# basic_attiny85.net
KiCad netlist of a schematic drawn in EAGLE
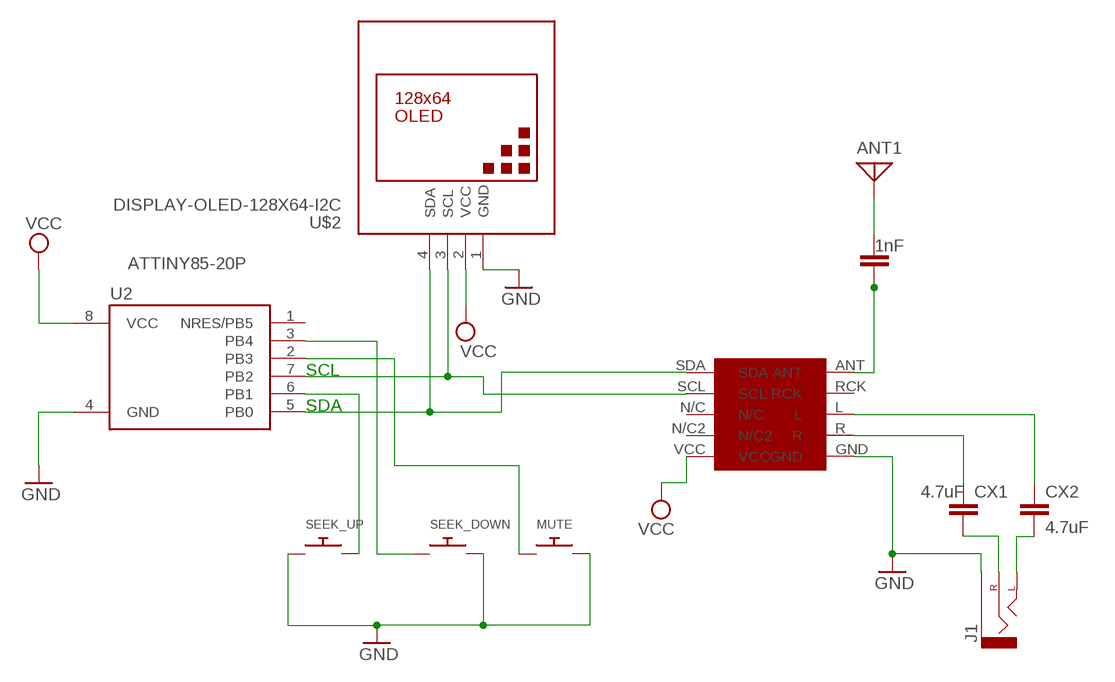
[diagram p0: schematic, sheet 1]

(export (version "E")
  (design (tool "Eeschema 10.0.6"))
  (components
    (comp (ref "ANT1")
      (value "ANTENNA")
      (footprint "eagle-import:PAD-01")
      (libsource (lib "eagle-import") (part "ANTENNA"))
    )
    (comp (ref "CX1")
      (value "4.7uF")
      (footprint "eagle-import:XC10B6")
      (libsource (lib "eagle-import") (part "CXXC10B6"))
    )
    (comp (ref "CX2")
      (value "4.7uF")
      (footprint "eagle-import:XC10B6")
      (libsource (lib "eagle-import") (part "CXXC10B6"))
    )
    (comp (ref "J1")
      (value "AUDIO_JACK_2.5MM_HOLESONLY")
      (footprint "eagle-import:STEREOJACK2.5MM_SPECIAL_HOLES-ONLY")
      (libsource (lib "eagle-import") (part "AUDIO_JACK_2.5MM_HOLESONLY"))
    )
    (comp (ref "MUTE")
      (value "SWITCH_PUSHBUTTONC&K_KSS")
      (footprint "eagle-import:BTN_CK_KSS")
      (libsource (lib "eagle-import") (part "SWITCH_PUSHBUTTONC&K_KSS"))
    )
    (comp (ref "SEEK_DOWN")
      (value "SWITCH_PUSHBUTTONC&K_KSS")
      (footprint "eagle-import:BTN_CK_KSS")
      (libsource (lib "eagle-import") (part "SWITCH_PUSHBUTTONC&K_KSS"))
    )
    (comp (ref "SEEK_UP")
      (value "SWITCH_PUSHBUTTONC&K_KSS")
      (footprint "eagle-import:BTN_CK_KSS")
      (libsource (lib "eagle-import") (part "SWITCH_PUSHBUTTONC&K_KSS"))
    )
    (comp (ref "U$1")
      (value "RDA")
      (footprint "eagle-import:RDA")
      (libsource (lib "eagle-import") (part "RDA"))
    )
    (comp (ref "U$2")
      (value "DISPLAY-OLED-128X64-I2C")
      (footprint "eagle-import:DISPLAY-OLED-128X64-I2C")
      (libsource (lib "eagle-import") (part "DISPLAY-OLED-128X64-I2C"))
    )
    (comp (ref "U2")
      (value "ATTINY85-20P")
      (footprint "eagle-import:PDIP08_300MIL")
      (libsource (lib "eagle-import") (part "ATTINY85P-20"))
    )
  )
  (nets
    (net (code "1") (name "GND") (class "Default")
      (node (ref "J1") (pin "RING1") (pinfunction "SLEEVE_RING1") (pintype "bidirectional"))
      (node (ref "MUTE") (pin "P$2") (pinfunction "P$2_P$2") (pintype "passive"))
      (node (ref "SEEK_DOWN") (pin "P$2") (pinfunction "P$2_P$2") (pintype "passive"))
      (node (ref "SEEK_UP") (pin "P$1") (pinfunction "P$1_P$1") (pintype "passive"))
      (node (ref "U$1") (pin "GND") (pinfunction "GND_GND") (pintype "power_in"))
      (node (ref "U$2") (pin "1") (pinfunction "GND_1") (pintype "power_in"))
      (node (ref "U2") (pin "4") (pinfunction "GND_4") (pintype "power_in"))
    )
    (net (code "2") (name "Net-(CX1-Pad1)") (class "Default")
      (node (ref "CX1") (pin "1") (pinfunction "1_1") (pintype "passive"))
      (node (ref "U$1") (pin "R") (pinfunction "R_R") (pintype "output"))
    )
    (net (code "3") (name "Net-(CX2-Pad1)") (class "Default")
      (node (ref "CX2") (pin "1") (pinfunction "1_1") (pintype "passive"))
      (node (ref "U$1") (pin "L") (pinfunction "L_L") (pintype "output"))
    )
    (net (code "4") (name "Net-(J1-LEFT)") (class "Default")
      (node (ref "CX2") (pin "2") (pinfunction "2_2") (pintype "passive"))
      (node (ref "J1") (pin "SHIELD") (pinfunction "LEFT_SHIELD") (pintype "bidirectional"))
    )
    (net (code "5") (name "Net-(J1-RIGHT)") (class "Default")
      (node (ref "CX1") (pin "2") (pinfunction "2_2") (pintype "passive"))
      (node (ref "J1") (pin "TIP") (pinfunction "RIGHT_TIP") (pintype "bidirectional"))
    )
    (net (code "6") (name "Net-(U$2-SCL)") (class "Default")
      (node (ref "U$1") (pin "SCL") (pinfunction "SCL_SCL") (pintype "bidirectional"))
      (node (ref "U$2") (pin "3") (pinfunction "SCL_3") (pintype "bidirectional"))
      (node (ref "U2") (pin "7") (pinfunction "PB2_7") (pintype "bidirectional"))
    )
    (net (code "7") (name "Net-(U$2-SDA)") (class "Default")
      (node (ref "U$1") (pin "SDA") (pinfunction "SDA_SDA") (pintype "bidirectional"))
      (node (ref "U$2") (pin "4") (pinfunction "SDA_4") (pintype "bidirectional"))
      (node (ref "U2") (pin "5") (pinfunction "PB0_5") (pintype "bidirectional"))
    )
    (net (code "8") (name "Net-(U2-PB1)") (class "Default")
      (node (ref "SEEK_UP") (pin "P$2") (pinfunction "P$2_P$2") (pintype "passive"))
      (node (ref "U2") (pin "6") (pinfunction "PB1_6") (pintype "bidirectional"))
    )
    (net (code "9") (name "Net-(U2-PB3)") (class "Default")
      (node (ref "MUTE") (pin "P$1") (pinfunction "P$1_P$1") (pintype "passive"))
      (node (ref "U2") (pin "2") (pinfunction "PB3_2") (pintype "bidirectional"))
    )
    (net (code "10") (name "Net-(U2-PB4)") (class "Default")
      (node (ref "SEEK_DOWN") (pin "P$1") (pinfunction "P$1_P$1") (pintype "passive"))
      (node (ref "U2") (pin "3") (pinfunction "PB4_3") (pintype "bidirectional"))
    )
    (net (code "11") (name "VCC") (class "Default")
      (node (ref "U$1") (pin "VCC") (pinfunction "VCC_VCC") (pintype "power_in"))
      (node (ref "U$2") (pin "2") (pinfunction "VCC_2") (pintype "power_in"))
      (node (ref "U2") (pin "8") (pinfunction "VCC_8") (pintype "power_in"))
    )
    (net (code "12") (name "unconnected-(ANT1-Pad1)") (class "Default")
      (node (ref "ANT1") (pin "1") (pinfunction "1_1") (pintype "output"))
    )
    (net (code "13") (name "unconnected-(U$1-PadANT)") (class "Default")
      (node (ref "U$1") (pin "ANT") (pinfunction "ANT_ANT") (pintype "input"))
    )
    (net (code "14") (name "unconnected-(U$1-PadN{slash}C)") (class "Default")
      (node (ref "U$1") (pin "N/C") (pinfunction "N/C_N/C") (pintype "passive"))
    )
    (net (code "15") (name "unconnected-(U$1-PadN{slash}C2)") (class "Default")
      (node (ref "U$1") (pin "N/C2") (pinfunction "N/C2_N/C2") (pintype "passive"))
    )
    (net (code "16") (name "unconnected-(U$1-PadRCK)") (class "Default")
      (node (ref "U$1") (pin "RCK") (pinfunction "RCK_RCK") (pintype "bidirectional"))
    )
    (net (code "17") (name "unconnected-(U2-NRES{slash}PB5-Pad1)") (class "Default")
      (node (ref "U2") (pin "1") (pinfunction "NRES/PB5_1") (pintype "bidirectional"))
    )
  )
)
